# Input_messenger.net
KiCad netlist of a schematic drawn in Altium Designer
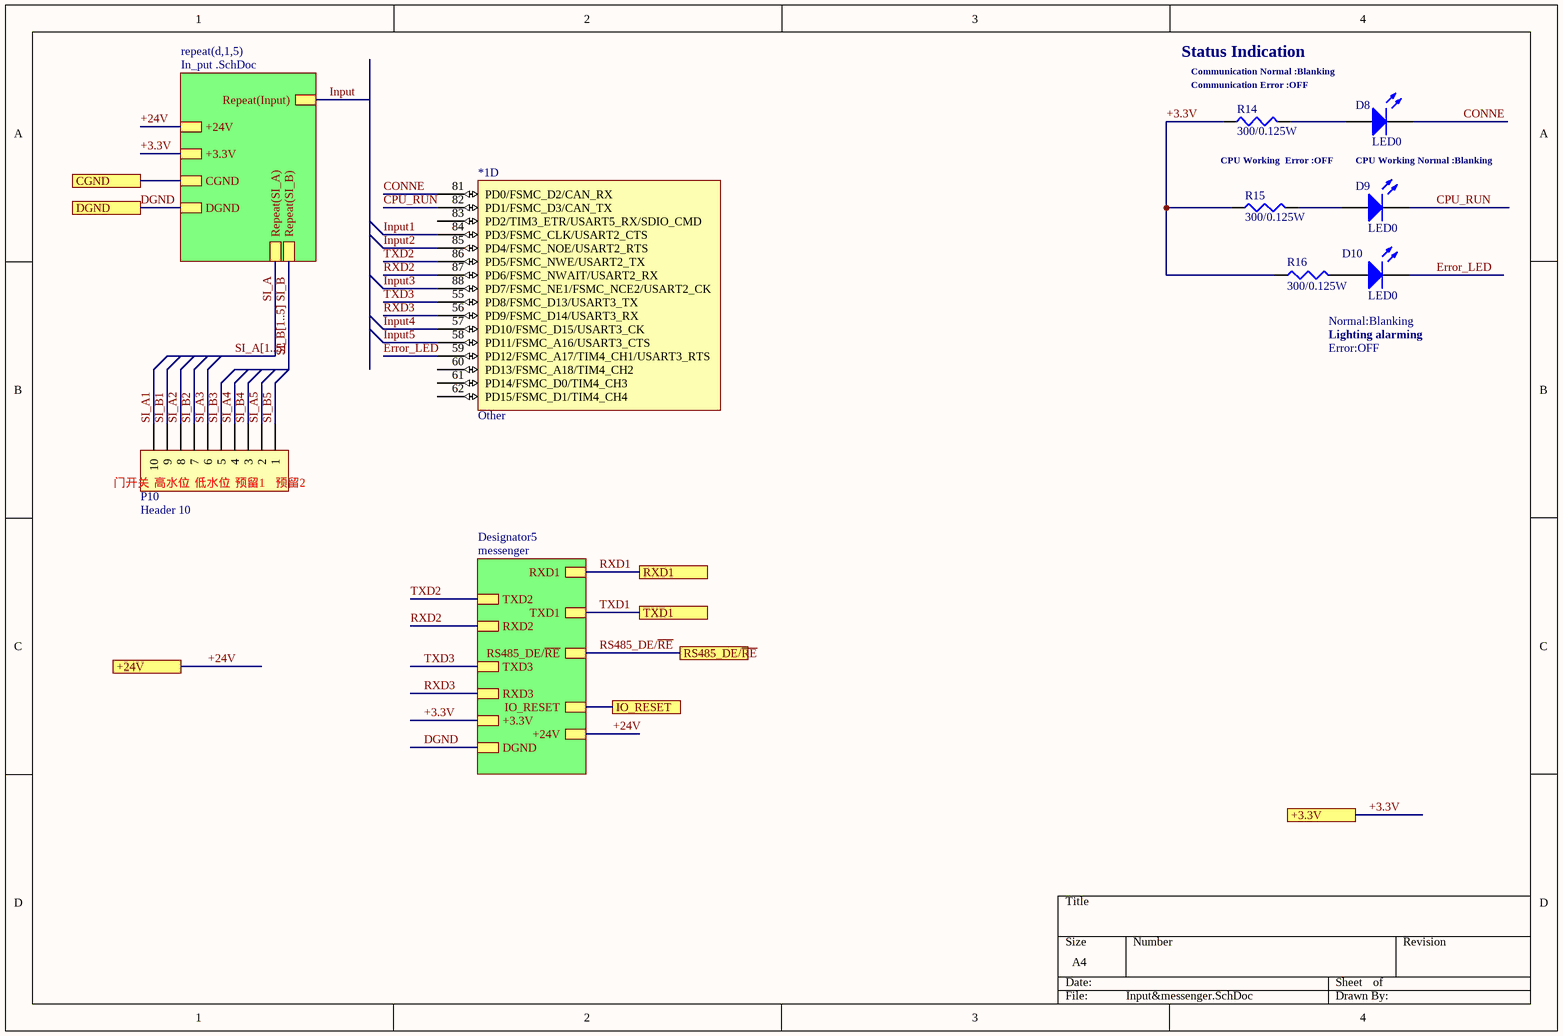
[diagram p0: Input&messenger.SchDoc]

(export (version "E")
  (design (tool "Eeschema 10.0.6"))
  (components
    (comp (ref "*1")
      (value "Other")
      (footprint "STM-LQFP100_N")
      (libsource (lib "原理图") (part "stm32f103vct6"))
    )
    (comp (ref "D8")
      (value "LED0")
      (footprint "0805LED")
      (fields (field (name "PUBLISHER") "Altium Limited"))
      (libsource (lib "Miscellaneous Devices") (part "LED0"))
    )
    (comp (ref "D9")
      (value "LED0")
      (footprint "0805LED")
      (fields (field (name "PUBLISHER") "Altium Limited"))
      (libsource (lib "Miscellaneous Devices") (part "LED0"))
    )
    (comp (ref "D10")
      (value "LED0")
      (footprint "0805LED")
      (fields (field (name "PUBLISHER") "Altium Limited"))
      (libsource (lib "Miscellaneous Devices") (part "LED0"))
    )
    (comp (ref "P10")
      (value "Header 10")
      (footprint "CONN-TH-KF7.62-10P")
      (fields (field (name "PUBLISHER") "Altium Limited"))
      (libsource (lib "Miscellaneous Connectors") (part "Header 10"))
    )
    (comp (ref "R14")
      (value "300/0.125W")
      (footprint "0805R")
      (description "品牌： UNI-ROYAL(厚声)    型号： 0805W8F3000T5E    电阻类型：厚膜电阻 阻值：300Ω 精度：±1% 功率：125mW 温度系数：±100ppm/℃")
      (libsource (lib "*") (part "RES1"))
    )
    (comp (ref "R15")
      (value "300/0.125W")
      (footprint "0805R")
      (description "品牌： UNI-ROYAL(厚声)    型号： 0805W8F3000T5E    电阻类型：厚膜电阻 阻值：300Ω 精度：±1% 功率：125mW 温度系数：±100ppm/℃")
      (libsource (lib "*") (part "RES1"))
    )
    (comp (ref "R16")
      (value "300/0.125W")
      (footprint "0805R")
      (description "品牌： UNI-ROYAL(厚声)    型号： 0805W8F3000T5E    电阻类型：厚膜电阻 阻值：300Ω 精度：±1% 功率：125mW 温度系数：±100ppm/℃")
      (libsource (lib "*") (part "RES1"))
    )
  )
  (nets
    (net (code "1") (name "/+3.3V") (class "Default")
      (node (ref "R14") (pin "1") (pinfunction "1_1") (pintype "passive"))
      (node (ref "R15") (pin "1") (pinfunction "1_1") (pintype "passive"))
      (node (ref "R16") (pin "1") (pinfunction "1_1") (pintype "passive"))
    )
    (net (code "4") (name "/CONNE") (class "Default")
      (node (ref "*1") (pin "81") (pinfunction "PD0/FSMC_D2/CAN_RX_81") (pintype "bidirectional"))
      (node (ref "D8") (pin "2") (pinfunction "K_2") (pintype "passive"))
    )
    (net (code "5") (name "/CPU_RUN") (class "Default")
      (node (ref "*1") (pin "82") (pinfunction "PD1/FSMC_D3/CAN_TX_82") (pintype "bidirectional"))
      (node (ref "D9") (pin "2") (pinfunction "K_2") (pintype "passive"))
    )
    (net (code "7") (name "/Error_LED") (class "Default")
      (node (ref "*1") (pin "59") (pinfunction "PD12/FSMC_A17/TIM4_CH1/USART3_RTS_59") (pintype "bidirectional"))
      (node (ref "D10") (pin "2") (pinfunction "K_2") (pintype "passive"))
    )
    (net (code "10") (name "/Input1") (class "Default")
      (node (ref "*1") (pin "84") (pinfunction "PD3/FSMC_CLK/USART2_CTS_84") (pintype "bidirectional"))
    )
    (net (code "11") (name "/Input2") (class "Default")
      (node (ref "*1") (pin "85") (pinfunction "PD4/FSMC_NOE/USART2_RTS_85") (pintype "bidirectional"))
    )
    (net (code "12") (name "/Input3") (class "Default")
      (node (ref "*1") (pin "88") (pinfunction "PD7/FSMC_NE1/FSMC_NCE2/USART2_CK_88") (pintype "bidirectional"))
    )
    (net (code "13") (name "/Input4") (class "Default")
      (node (ref "*1") (pin "57") (pinfunction "PD10/FSMC_D15/USART3_CK_57") (pintype "bidirectional"))
    )
    (net (code "14") (name "/Input5") (class "Default")
      (node (ref "*1") (pin "58") (pinfunction "PD11/FSMC_A16/USART3_CTS_58") (pintype "bidirectional"))
    )
    (net (code "17") (name "/RXD2") (class "Default")
      (node (ref "*1") (pin "87") (pinfunction "PD6/FSMC_NWAIT/USART2_RX_87") (pintype "bidirectional"))
    )
    (net (code "18") (name "/RXD3") (class "Default")
      (node (ref "*1") (pin "56") (pinfunction "PD9/FSMC_D14/USART3_RX_56") (pintype "bidirectional"))
    )
    (net (code "20") (name "/SI_A1") (class "Default")
      (node (ref "P10") (pin "10") (pinfunction "10_10") (pintype "passive"))
    )
    (net (code "21") (name "/SI_A2") (class "Default")
      (node (ref "P10") (pin "8") (pinfunction "8_8") (pintype "passive"))
    )
    (net (code "22") (name "/SI_A3") (class "Default")
      (node (ref "P10") (pin "6") (pinfunction "6_6") (pintype "passive"))
    )
    (net (code "23") (name "/SI_A4") (class "Default")
      (node (ref "P10") (pin "4") (pinfunction "4_4") (pintype "passive"))
    )
    (net (code "24") (name "/SI_A5") (class "Default")
      (node (ref "P10") (pin "2") (pinfunction "2_2") (pintype "passive"))
    )
    (net (code "27") (name "/SI_B1") (class "Default")
      (node (ref "P10") (pin "9") (pinfunction "9_9") (pintype "passive"))
    )
    (net (code "28") (name "/SI_B2") (class "Default")
      (node (ref "P10") (pin "7") (pinfunction "7_7") (pintype "passive"))
    )
    (net (code "29") (name "/SI_B3") (class "Default")
      (node (ref "P10") (pin "5") (pinfunction "5_5") (pintype "passive"))
    )
    (net (code "30") (name "/SI_B4") (class "Default")
      (node (ref "P10") (pin "3") (pinfunction "3_3") (pintype "passive"))
    )
    (net (code "31") (name "/SI_B5") (class "Default")
      (node (ref "P10") (pin "1") (pinfunction "1_1") (pintype "passive"))
    )
    (net (code "34") (name "/TXD2") (class "Default")
      (node (ref "*1") (pin "86") (pinfunction "PD5/FSMC_NWE/USART2_TX_86") (pintype "bidirectional"))
    )
    (net (code "35") (name "/TXD3") (class "Default")
      (node (ref "*1") (pin "55") (pinfunction "PD8/FSMC_D13/USART3_TX_55") (pintype "bidirectional"))
    )
    (net (code "36") (name "Net-(D8-A)") (class "Default")
      (node (ref "D8") (pin "1") (pinfunction "A_1") (pintype "passive"))
      (node (ref "R14") (pin "2") (pinfunction "2_2") (pintype "passive"))
    )
    (net (code "37") (name "Net-(D9-A)") (class "Default")
      (node (ref "D9") (pin "1") (pinfunction "A_1") (pintype "passive"))
      (node (ref "R15") (pin "2") (pinfunction "2_2") (pintype "passive"))
    )
    (net (code "38") (name "Net-(D10-A)") (class "Default")
      (node (ref "D10") (pin "1") (pinfunction "A_1") (pintype "passive"))
      (node (ref "R16") (pin "2") (pinfunction "2_2") (pintype "passive"))
    )
    (net (code "39") (name "unconnected-(*1D-PD2{slash}TIM3_ETR{slash}USART5_RX{slash}SDIO_CMD-Pad83)") (class "Default")
      (node (ref "*1") (pin "83") (pinfunction "PD2/TIM3_ETR/USART5_RX/SDIO_CMD_83") (pintype "bidirectional"))
    )
    (net (code "40") (name "unconnected-(*1D-PD13{slash}FSMC_A18{slash}TIM4_CH2-Pad60)") (class "Default")
      (node (ref "*1") (pin "60") (pinfunction "PD13/FSMC_A18/TIM4_CH2_60") (pintype "bidirectional"))
    )
    (net (code "41") (name "unconnected-(*1D-PD14{slash}FSMC_D0{slash}TIM4_CH3-Pad61)") (class "Default")
      (node (ref "*1") (pin "61") (pinfunction "PD14/FSMC_D0/TIM4_CH3_61") (pintype "bidirectional"))
    )
    (net (code "42") (name "unconnected-(*1D-PD15{slash}FSMC_D1{slash}TIM4_CH4-Pad62)") (class "Default")
      (node (ref "*1") (pin "62") (pinfunction "PD15/FSMC_D1/TIM4_CH4_62") (pintype "bidirectional"))
    )
  )
)
